# Shopfloor_HP_Molex_NEW.net
KiCad netlist of a schematic drawn in EAGLE
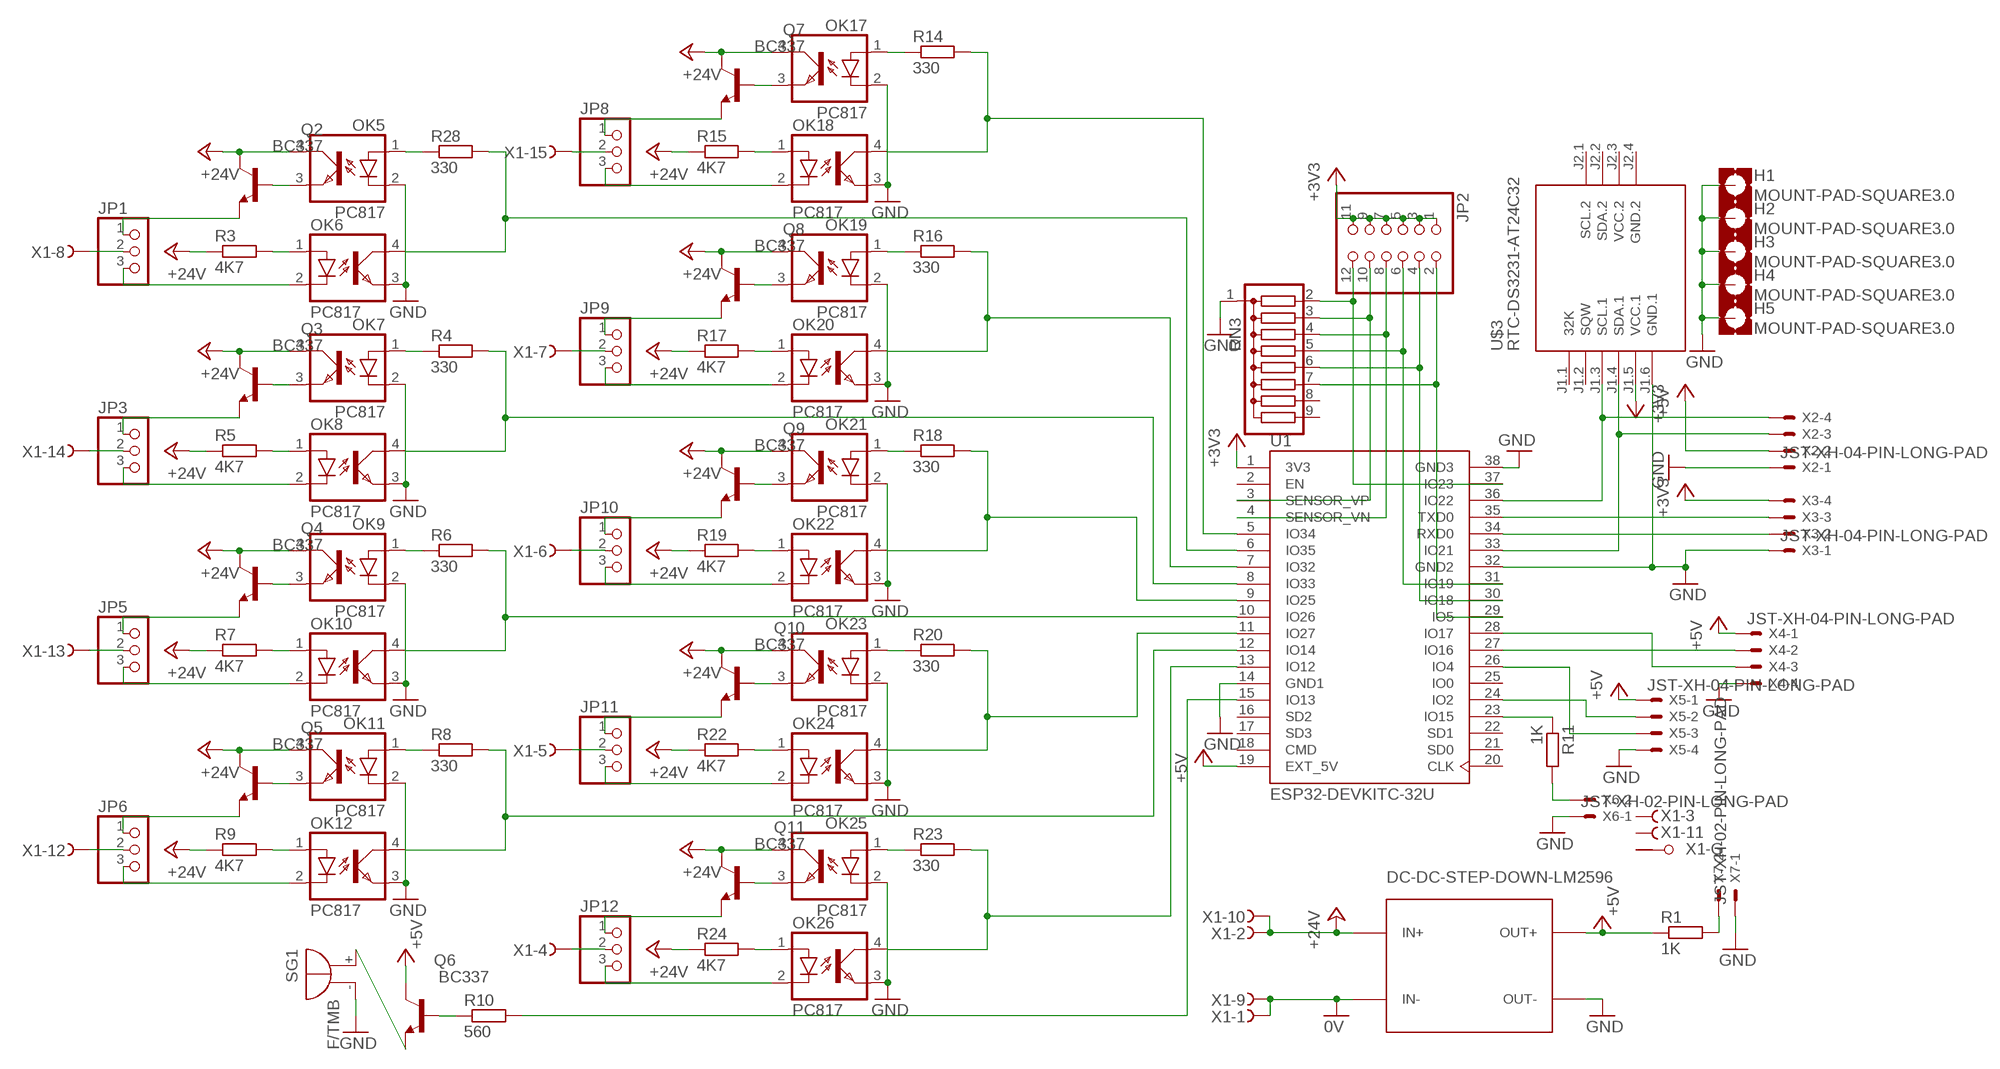
[diagram p0: schematic, sheet 1]

(export (version "E")
  (design (tool "Eeschema 10.0.6"))
  (components
    (comp (ref "H1")
      (value "MOUNT-PAD-SQUARE3.0")
      (footprint "eagle-import:3,0-PAD-SQUARE")
      (libsource (lib "eagle-import") (part "MOUNT-PAD-SQUARE3.0"))
    )
    (comp (ref "H2")
      (value "MOUNT-PAD-SQUARE3.0")
      (footprint "eagle-import:3,0-PAD-SQUARE")
      (libsource (lib "eagle-import") (part "MOUNT-PAD-SQUARE3.0"))
    )
    (comp (ref "H3")
      (value "MOUNT-PAD-SQUARE3.0")
      (footprint "eagle-import:3,0-PAD-SQUARE")
      (libsource (lib "eagle-import") (part "MOUNT-PAD-SQUARE3.0"))
    )
    (comp (ref "H4")
      (value "MOUNT-PAD-SQUARE3.0")
      (footprint "eagle-import:3,0-PAD-SQUARE")
      (libsource (lib "eagle-import") (part "MOUNT-PAD-SQUARE3.0"))
    )
    (comp (ref "H5")
      (value "MOUNT-PAD-SQUARE3.0")
      (footprint "eagle-import:3,0-PAD-SQUARE")
      (libsource (lib "eagle-import") (part "MOUNT-PAD-SQUARE3.0"))
    )
    (comp (ref "JP1")
      (value "PINHD-1X3")
      (footprint "eagle-import:1X03")
      (libsource (lib "eagle-import") (part "PINHD-1X3"))
    )
    (comp (ref "JP2")
      (value "PINHD-2X6")
      (footprint "eagle-import:2X06")
      (libsource (lib "eagle-import") (part "PINHD-2X6"))
    )
    (comp (ref "JP3")
      (value "PINHD-1X3")
      (footprint "eagle-import:1X03")
      (libsource (lib "eagle-import") (part "PINHD-1X3"))
    )
    (comp (ref "JP5")
      (value "PINHD-1X3")
      (footprint "eagle-import:1X03")
      (libsource (lib "eagle-import") (part "PINHD-1X3"))
    )
    (comp (ref "JP6")
      (value "PINHD-1X3")
      (footprint "eagle-import:1X03")
      (libsource (lib "eagle-import") (part "PINHD-1X3"))
    )
    (comp (ref "JP8")
      (value "PINHD-1X3")
      (footprint "eagle-import:1X03")
      (libsource (lib "eagle-import") (part "PINHD-1X3"))
    )
    (comp (ref "JP9")
      (value "PINHD-1X3")
      (footprint "eagle-import:1X03")
      (libsource (lib "eagle-import") (part "PINHD-1X3"))
    )
    (comp (ref "JP10")
      (value "PINHD-1X3")
      (footprint "eagle-import:1X03")
      (libsource (lib "eagle-import") (part "PINHD-1X3"))
    )
    (comp (ref "JP11")
      (value "PINHD-1X3")
      (footprint "eagle-import:1X03")
      (libsource (lib "eagle-import") (part "PINHD-1X3"))
    )
    (comp (ref "JP12")
      (value "PINHD-1X3")
      (footprint "eagle-import:1X03")
      (libsource (lib "eagle-import") (part "PINHD-1X3"))
    )
    (comp (ref "OK5")
      (value "PC817")
      (footprint "eagle-import:DIL04")
      (fields (field (name "MPN") "PC817X4J000F"))
      (libsource (lib "eagle-import") (part "PC817"))
    )
    (comp (ref "OK6")
      (value "PC817")
      (footprint "eagle-import:DIL04")
      (fields (field (name "MPN") "PC817X4J000F"))
      (libsource (lib "eagle-import") (part "PC817"))
    )
    (comp (ref "OK7")
      (value "PC817")
      (footprint "eagle-import:DIL04")
      (fields (field (name "MPN") "PC817X4J000F"))
      (libsource (lib "eagle-import") (part "PC817"))
    )
    (comp (ref "OK8")
      (value "PC817")
      (footprint "eagle-import:DIL04")
      (fields (field (name "MPN") "PC817X4J000F"))
      (libsource (lib "eagle-import") (part "PC817"))
    )
    (comp (ref "OK9")
      (value "PC817")
      (footprint "eagle-import:DIL04")
      (fields (field (name "MPN") "PC817X4J000F"))
      (libsource (lib "eagle-import") (part "PC817"))
    )
    (comp (ref "OK10")
      (value "PC817")
      (footprint "eagle-import:DIL04")
      (fields (field (name "MPN") "PC817X4J000F"))
      (libsource (lib "eagle-import") (part "PC817"))
    )
    (comp (ref "OK11")
      (value "PC817")
      (footprint "eagle-import:DIL04")
      (fields (field (name "MPN") "PC817X4J000F"))
      (libsource (lib "eagle-import") (part "PC817"))
    )
    (comp (ref "OK12")
      (value "PC817")
      (footprint "eagle-import:DIL04")
      (fields (field (name "MPN") "PC817X4J000F"))
      (libsource (lib "eagle-import") (part "PC817"))
    )
    (comp (ref "OK17")
      (value "PC817")
      (footprint "eagle-import:DIL04")
      (fields (field (name "MPN") "PC817X4J000F"))
      (libsource (lib "eagle-import") (part "PC817"))
    )
    (comp (ref "OK18")
      (value "PC817")
      (footprint "eagle-import:DIL04")
      (fields (field (name "MPN") "PC817X4J000F"))
      (libsource (lib "eagle-import") (part "PC817"))
    )
    (comp (ref "OK19")
      (value "PC817")
      (footprint "eagle-import:DIL04")
      (fields (field (name "MPN") "PC817X4J000F"))
      (libsource (lib "eagle-import") (part "PC817"))
    )
    (comp (ref "OK20")
      (value "PC817")
      (footprint "eagle-import:DIL04")
      (fields (field (name "MPN") "PC817X4J000F"))
      (libsource (lib "eagle-import") (part "PC817"))
    )
    (comp (ref "OK21")
      (value "PC817")
      (footprint "eagle-import:DIL04")
      (fields (field (name "MPN") "PC817X4J000F"))
      (libsource (lib "eagle-import") (part "PC817"))
    )
    (comp (ref "OK22")
      (value "PC817")
      (footprint "eagle-import:DIL04")
      (fields (field (name "MPN") "PC817X4J000F"))
      (libsource (lib "eagle-import") (part "PC817"))
    )
    (comp (ref "OK23")
      (value "PC817")
      (footprint "eagle-import:DIL04")
      (fields (field (name "MPN") "PC817X4J000F"))
      (libsource (lib "eagle-import") (part "PC817"))
    )
    (comp (ref "OK24")
      (value "PC817")
      (footprint "eagle-import:DIL04")
      (fields (field (name "MPN") "PC817X4J000F"))
      (libsource (lib "eagle-import") (part "PC817"))
    )
    (comp (ref "OK25")
      (value "PC817")
      (footprint "eagle-import:DIL04")
      (fields (field (name "MPN") "PC817X4J000F"))
      (libsource (lib "eagle-import") (part "PC817"))
    )
    (comp (ref "OK26")
      (value "PC817")
      (footprint "eagle-import:DIL04")
      (fields (field (name "MPN") "PC817X4J000F"))
      (libsource (lib "eagle-import") (part "PC817"))
    )
    (comp (ref "Q2")
      (value "BC337")
      (footprint "eagle-import:TO92")
      (libsource (lib "eagle-import") (part "BC337"))
    )
    (comp (ref "Q3")
      (value "BC337")
      (footprint "eagle-import:TO92")
      (libsource (lib "eagle-import") (part "BC337"))
    )
    (comp (ref "Q4")
      (value "BC337")
      (footprint "eagle-import:TO92")
      (libsource (lib "eagle-import") (part "BC337"))
    )
    (comp (ref "Q5")
      (value "BC337")
      (footprint "eagle-import:TO92")
      (libsource (lib "eagle-import") (part "BC337"))
    )
    (comp (ref "Q6")
      (value "BC337")
      (footprint "eagle-import:TO92")
      (libsource (lib "eagle-import") (part "BC337"))
    )
    (comp (ref "Q7")
      (value "BC337")
      (footprint "eagle-import:TO92")
      (libsource (lib "eagle-import") (part "BC337"))
    )
    (comp (ref "Q8")
      (value "BC337")
      (footprint "eagle-import:TO92")
      (libsource (lib "eagle-import") (part "BC337"))
    )
    (comp (ref "Q9")
      (value "BC337")
      (footprint "eagle-import:TO92")
      (libsource (lib "eagle-import") (part "BC337"))
    )
    (comp (ref "Q10")
      (value "BC337")
      (footprint "eagle-import:TO92")
      (libsource (lib "eagle-import") (part "BC337"))
    )
    (comp (ref "Q11")
      (value "BC337")
      (footprint "eagle-import:TO92")
      (libsource (lib "eagle-import") (part "BC337"))
    )
    (comp (ref "R1")
      (value "1K")
      (footprint "eagle-import:0207_7")
      (libsource (lib "eagle-import") (part "R-EU_0207/7"))
    )
    (comp (ref "R3")
      (value "4K7")
      (footprint "eagle-import:0207_7")
      (libsource (lib "eagle-import") (part "R-EU_0207/7"))
    )
    (comp (ref "R4")
      (value "330")
      (footprint "eagle-import:0207_7")
      (libsource (lib "eagle-import") (part "R-EU_0207/7"))
    )
    (comp (ref "R5")
      (value "4K7")
      (footprint "eagle-import:0207_7")
      (libsource (lib "eagle-import") (part "R-EU_0207/7"))
    )
    (comp (ref "R6")
      (value "330")
      (footprint "eagle-import:0207_7")
      (libsource (lib "eagle-import") (part "R-EU_0207/7"))
    )
    (comp (ref "R7")
      (value "4K7")
      (footprint "eagle-import:0207_7")
      (libsource (lib "eagle-import") (part "R-EU_0207/7"))
    )
    (comp (ref "R8")
      (value "330")
      (footprint "eagle-import:0207_7")
      (libsource (lib "eagle-import") (part "R-EU_0207/7"))
    )
    (comp (ref "R9")
      (value "4K7")
      (footprint "eagle-import:0207_7")
      (libsource (lib "eagle-import") (part "R-EU_0207/7"))
    )
    (comp (ref "R10")
      (value "560")
      (footprint "eagle-import:0207_7")
      (libsource (lib "eagle-import") (part "R-EU_0207/7"))
    )
    (comp (ref "R11")
      (value "1K")
      (footprint "eagle-import:0207_7")
      (libsource (lib "eagle-import") (part "R-EU_0207/7"))
    )
    (comp (ref "R14")
      (value "330")
      (footprint "eagle-import:0207_7")
      (libsource (lib "eagle-import") (part "R-EU_0207/7"))
    )
    (comp (ref "R15")
      (value "4K7")
      (footprint "eagle-import:0207_7")
      (libsource (lib "eagle-import") (part "R-EU_0207/7"))
    )
    (comp (ref "R16")
      (value "330")
      (footprint "eagle-import:0207_7")
      (libsource (lib "eagle-import") (part "R-EU_0207/7"))
    )
    (comp (ref "R17")
      (value "4K7")
      (footprint "eagle-import:0207_7")
      (libsource (lib "eagle-import") (part "R-EU_0207/7"))
    )
    (comp (ref "R18")
      (value "330")
      (footprint "eagle-import:0207_7")
      (libsource (lib "eagle-import") (part "R-EU_0207/7"))
    )
    (comp (ref "R19")
      (value "4K7")
      (footprint "eagle-import:0207_7")
      (libsource (lib "eagle-import") (part "R-EU_0207/7"))
    )
    (comp (ref "R20")
      (value "330")
      (footprint "eagle-import:0207_7")
      (libsource (lib "eagle-import") (part "R-EU_0207/7"))
    )
    (comp (ref "R22")
      (value "4K7")
      (footprint "eagle-import:0207_7")
      (libsource (lib "eagle-import") (part "R-EU_0207/7"))
    )
    (comp (ref "R23")
      (value "330")
      (footprint "eagle-import:0207_7")
      (libsource (lib "eagle-import") (part "R-EU_0207/7"))
    )
    (comp (ref "R24")
      (value "4K7")
      (footprint "eagle-import:0207_7")
      (libsource (lib "eagle-import") (part "R-EU_0207/7"))
    )
    (comp (ref "R28")
      (value "330")
      (footprint "eagle-import:0207_7")
      (libsource (lib "eagle-import") (part "R-EU_0207/7"))
    )
    (comp (ref "RN3")
      (value "G08R")
      (footprint "eagle-import:SIL9")
      (libsource (lib "eagle-import") (part "G08R"))
    )
    (comp (ref "SG1")
      (value "F/TMB")
      (footprint "eagle-import:F_TMB")
      (libsource (lib "eagle-import") (part "F/TMB"))
    )
    (comp (ref "U$1")
      (value "DC-DC-STEP-DOWN-LM2596")
      (footprint "eagle-import:DC-DC-STEP-DOWN-LM2596")
      (libsource (lib "eagle-import") (part "DC-DC-STEP-DOWN-LM2596"))
    )
    (comp (ref "U$3")
      (value "RTC-DS3231-AT24C32")
      (footprint "eagle-import:RTC-DS3231-AT24C32")
      (libsource (lib "eagle-import") (part "RTC-DS3231-AT24C32"))
    )
    (comp (ref "U1")
      (value "ESP32-DEVKITC-32U")
      (footprint "eagle-import:MODULE_ESP32-DEVKITC-32U")
      (fields (field (name "MF") "Espressif Systems"))
      (libsource (lib "eagle-import") (part "ESP32-DEVKITC-32U"))
    )
    (comp (ref "X1")
      (value "F15HPS")
      (footprint "eagle-import:F15HP")
      (libsource (lib "eagle-import") (part "F15HPS"))
    )
    (comp (ref "X2")
      (value "JST-XH-04-PIN-LONG-PAD")
      (footprint "eagle-import:JST-XH-04-PACKAGE-LONG-PAD")
      (libsource (lib "eagle-import") (part "JST-XH-04-PIN-LONG-PAD"))
    )
    (comp (ref "X3")
      (value "JST-XH-04-PIN-LONG-PAD")
      (footprint "eagle-import:JST-XH-04-PACKAGE-LONG-PAD")
      (libsource (lib "eagle-import") (part "JST-XH-04-PIN-LONG-PAD"))
    )
    (comp (ref "X4")
      (value "JST-XH-04-PIN-LONG-PAD")
      (footprint "eagle-import:JST-XH-04-PACKAGE-LONG-PAD")
      (libsource (lib "eagle-import") (part "JST-XH-04-PIN-LONG-PAD"))
    )
    (comp (ref "X5")
      (value "JST-XH-04-PIN-LONG-PAD")
      (footprint "eagle-import:JST-XH-04-PACKAGE-LONG-PAD")
      (libsource (lib "eagle-import") (part "JST-XH-04-PIN-LONG-PAD"))
    )
    (comp (ref "X6")
      (value "JST-XH-02-PIN-LONG-PAD")
      (footprint "eagle-import:JST-XH-02-PACKAGE-LONG-PAD")
      (libsource (lib "eagle-import") (part "JST-XH-02-PIN-LONG-PAD"))
    )
    (comp (ref "X7")
      (value "JST-XH-02-PIN-LONG-PAD")
      (footprint "eagle-import:JST-XH-02-PACKAGE-LONG-PAD")
      (libsource (lib "eagle-import") (part "JST-XH-02-PIN-LONG-PAD"))
    )
  )
  (nets
    (net (code "1") (name "+3V3") (class "Default")
      (node (ref "JP2") (pin "1") (pinfunction "1_1") (pintype "passive"))
      (node (ref "JP2") (pin "11") (pinfunction "11_11") (pintype "passive"))
      (node (ref "JP2") (pin "3") (pinfunction "3_3") (pintype "passive"))
      (node (ref "JP2") (pin "5") (pinfunction "5_5") (pintype "passive"))
      (node (ref "JP2") (pin "7") (pinfunction "7_7") (pintype "passive"))
      (node (ref "JP2") (pin "9") (pinfunction "9_9") (pintype "passive"))
      (node (ref "U$3") (pin "J1.5") (pinfunction "VCC.1_J1.5") (pintype "power_in"))
      (node (ref "U1") (pin "1") (pinfunction "3V3_1") (pintype "power_in"))
      (node (ref "X3") (pin "4") (pinfunction "S_4") (pintype "passive"))
    )
    (net (code "2") (name "+5V") (class "Default")
      (node (ref "Q6") (pin "3") (pinfunction "C_3") (pintype "passive"))
      (node (ref "R1") (pin "1") (pinfunction "1_1") (pintype "passive"))
      (node (ref "U$1") (pin "OUT+") (pinfunction "OUT+_OUT+") (pintype "bidirectional"))
      (node (ref "U1") (pin "19") (pinfunction "EXT_5V_19") (pintype "power_in"))
      (node (ref "X2") (pin "2") (pinfunction "S_2") (pintype "passive"))
      (node (ref "X4") (pin "1") (pinfunction "S_1") (pintype "passive"))
      (node (ref "X5") (pin "1") (pinfunction "S_1") (pintype "passive"))
    )
    (net (code "3") (name "+24V") (class "Default")
      (node (ref "OK11") (pin "4") (pinfunction "COL_4") (pintype "passive"))
      (node (ref "OK17") (pin "4") (pinfunction "COL_4") (pintype "passive"))
      (node (ref "OK19") (pin "4") (pinfunction "COL_4") (pintype "passive"))
      (node (ref "OK21") (pin "4") (pinfunction "COL_4") (pintype "passive"))
      (node (ref "OK23") (pin "4") (pinfunction "COL_4") (pintype "passive"))
      (node (ref "OK25") (pin "4") (pinfunction "COL_4") (pintype "passive"))
      (node (ref "OK5") (pin "4") (pinfunction "COL_4") (pintype "passive"))
      (node (ref "OK7") (pin "4") (pinfunction "COL_4") (pintype "passive"))
      (node (ref "OK9") (pin "4") (pinfunction "COL_4") (pintype "passive"))
      (node (ref "Q10") (pin "3") (pinfunction "C_3") (pintype "passive"))
      (node (ref "Q11") (pin "3") (pinfunction "C_3") (pintype "passive"))
      (node (ref "Q2") (pin "3") (pinfunction "C_3") (pintype "passive"))
      (node (ref "Q3") (pin "3") (pinfunction "C_3") (pintype "passive"))
      (node (ref "Q4") (pin "3") (pinfunction "C_3") (pintype "passive"))
      (node (ref "Q5") (pin "3") (pinfunction "C_3") (pintype "passive"))
      (node (ref "Q7") (pin "3") (pinfunction "C_3") (pintype "passive"))
      (node (ref "Q8") (pin "3") (pinfunction "C_3") (pintype "passive"))
      (node (ref "Q9") (pin "3") (pinfunction "C_3") (pintype "passive"))
      (node (ref "R15") (pin "1") (pinfunction "1_1") (pintype "passive"))
      (node (ref "R17") (pin "1") (pinfunction "1_1") (pintype "passive"))
      (node (ref "R19") (pin "1") (pinfunction "1_1") (pintype "passive"))
      (node (ref "R22") (pin "1") (pinfunction "1_1") (pintype "passive"))
      (node (ref "R24") (pin "1") (pinfunction "1_1") (pintype "passive"))
      (node (ref "R3") (pin "1") (pinfunction "1_1") (pintype "passive"))
      (node (ref "R5") (pin "1") (pinfunction "1_1") (pintype "passive"))
      (node (ref "R7") (pin "1") (pinfunction "1_1") (pintype "passive"))
      (node (ref "R9") (pin "1") (pinfunction "1_1") (pintype "passive"))
      (node (ref "U$1") (pin "IN+") (pinfunction "IN+_IN+") (pintype "bidirectional"))
      (node (ref "X1") (pin "10") (pinfunction "F_10") (pintype "passive"))
      (node (ref "X1") (pin "2") (pinfunction "F_2") (pintype "passive"))
    )
    (net (code "4") (name "/GND.2") (class "Default")
      (node (ref "U$3") (pin "J2.4") (pinfunction "GND.2_J2.4") (pintype "power_in"))
    )
    (net (code "5") (name "/VCC.2") (class "Default")
      (node (ref "U$3") (pin "J2.3") (pinfunction "VCC.2_J2.3") (pintype "power_in"))
    )
    (net (code "6") (name "0V") (class "Default")
      (node (ref "U$1") (pin "IN-") (pinfunction "IN-_IN-") (pintype "bidirectional"))
      (node (ref "X1") (pin "1") (pinfunction "F_1") (pintype "passive"))
      (node (ref "X1") (pin "9") (pinfunction "F_9") (pintype "passive"))
    )
    (net (code "7") (name "GND") (class "Default")
      (node (ref "H1") (pin "B3,0") (pinfunction "MOUNT_B3,0") (pintype "passive"))
      (node (ref "H2") (pin "B3,0") (pinfunction "MOUNT_B3,0") (pintype "passive"))
      (node (ref "H3") (pin "B3,0") (pinfunction "MOUNT_B3,0") (pintype "passive"))
      (node (ref "H4") (pin "B3,0") (pinfunction "MOUNT_B3,0") (pintype "passive"))
      (node (ref "H5") (pin "B3,0") (pinfunction "MOUNT_B3,0") (pintype "passive"))
      (node (ref "OK10") (pin "3") (pinfunction "EMIT_3") (pintype "passive"))
      (node (ref "OK11") (pin "2") (pinfunction "C_2") (pintype "passive"))
      (node (ref "OK12") (pin "3") (pinfunction "EMIT_3") (pintype "passive"))
      (node (ref "OK17") (pin "2") (pinfunction "C_2") (pintype "passive"))
      (node (ref "OK18") (pin "3") (pinfunction "EMIT_3") (pintype "passive"))
      (node (ref "OK19") (pin "2") (pinfunction "C_2") (pintype "passive"))
      (node (ref "OK20") (pin "3") (pinfunction "EMIT_3") (pintype "passive"))
      (node (ref "OK21") (pin "2") (pinfunction "C_2") (pintype "passive"))
      (node (ref "OK22") (pin "3") (pinfunction "EMIT_3") (pintype "passive"))
      (node (ref "OK23") (pin "2") (pinfunction "C_2") (pintype "passive"))
      (node (ref "OK24") (pin "3") (pinfunction "EMIT_3") (pintype "passive"))
      (node (ref "OK25") (pin "2") (pinfunction "C_2") (pintype "passive"))
      (node (ref "OK26") (pin "3") (pinfunction "EMIT_3") (pintype "passive"))
      (node (ref "OK5") (pin "2") (pinfunction "C_2") (pintype "passive"))
      (node (ref "OK6") (pin "3") (pinfunction "EMIT_3") (pintype "passive"))
      (node (ref "OK7") (pin "2") (pinfunction "C_2") (pintype "passive"))
      (node (ref "OK8") (pin "3") (pinfunction "EMIT_3") (pintype "passive"))
      (node (ref "OK9") (pin "2") (pinfunction "C_2") (pintype "passive"))
      (node (ref "RN3") (pin "1") (pinfunction "1_1") (pintype "passive"))
      (node (ref "SG1") (pin "-") (pinfunction "-_-") (pintype "passive"))
      (node (ref "U$1") (pin "OUT-") (pinfunction "OUT-_OUT-") (pintype "bidirectional"))
      (node (ref "U$3") (pin "J1.6") (pinfunction "GND.1_J1.6") (pintype "power_in"))
      (node (ref "U1") (pin "14") (pinfunction "GND1_14") (pintype "power_in"))
      (node (ref "U1") (pin "32") (pinfunction "GND2_32") (pintype "power_in"))
      (node (ref "U1") (pin "38") (pinfunction "GND3_38") (pintype "power_in"))
      (node (ref "X2") (pin "1") (pinfunction "S_1") (pintype "passive"))
      (node (ref "X3") (pin "1") (pinfunction "S_1") (pintype "passive"))
      (node (ref "X4") (pin "4") (pinfunction "S_4") (pintype "passive"))
      (node (ref "X5") (pin "4") (pinfunction "S_4") (pintype "passive"))
      (node (ref "X6") (pin "1") (pinfunction "S_1") (pintype "passive"))
      (node (ref "X7") (pin "1") (pinfunction "S_1") (pintype "passive"))
    )
    (net (code "8") (name "Net-(OK5-A)") (class "Default")
      (node (ref "OK5") (pin "1") (pinfunction "A_1") (pintype "passive"))
      (node (ref "R28") (pin "1") (pinfunction "1_1") (pintype "passive"))
    )
    (net (code "9") (name "Net-(OK5-EMIT)") (class "Default")
      (node (ref "OK5") (pin "3") (pinfunction "EMIT_3") (pintype "passive"))
      (node (ref "Q2") (pin "2") (pinfunction "B_2") (pintype "passive"))
    )
    (net (code "10") (name "Net-(OK6-A)") (class "Default")
      (node (ref "OK6") (pin "1") (pinfunction "A_1") (pintype "passive"))
      (node (ref "R3") (pin "2") (pinfunction "2_2") (pintype "passive"))
    )
    (net (code "11") (name "Net-(OK6-C)") (class "Default")
      (node (ref "JP1") (pin "3") (pinfunction "3_3") (pintype "passive"))
      (node (ref "OK6") (pin "2") (pinfunction "C_2") (pintype "passive"))
    )
    (net (code "12") (name "Net-(OK6-COL)") (class "Default")
      (node (ref "OK6") (pin "4") (pinfunction "COL_4") (pintype "passive"))
      (node (ref "R28") (pin "2") (pinfunction "2_2") (pintype "passive"))
      (node (ref "U1") (pin "6") (pinfunction "IO35_6") (pintype "bidirectional"))
    )
    (net (code "13") (name "Net-(OK7-A)") (class "Default")
      (node (ref "OK7") (pin "1") (pinfunction "A_1") (pintype "passive"))
      (node (ref "R4") (pin "1") (pinfunction "1_1") (pintype "passive"))
    )
    (net (code "14") (name "Net-(OK7-EMIT)") (class "Default")
      (node (ref "OK7") (pin "3") (pinfunction "EMIT_3") (pintype "passive"))
      (node (ref "Q3") (pin "2") (pinfunction "B_2") (pintype "passive"))
    )
    (net (code "15") (name "Net-(OK8-A)") (class "Default")
      (node (ref "OK8") (pin "1") (pinfunction "A_1") (pintype "passive"))
      (node (ref "R5") (pin "2") (pinfunction "2_2") (pintype "passive"))
    )
    (net (code "16") (name "Net-(OK8-C)") (class "Default")
      (node (ref "JP3") (pin "3") (pinfunction "3_3") (pintype "passive"))
      (node (ref "OK8") (pin "2") (pinfunction "C_2") (pintype "passive"))
    )
    (net (code "17") (name "Net-(OK8-COL)") (class "Default")
      (node (ref "OK8") (pin "4") (pinfunction "COL_4") (pintype "passive"))
      (node (ref "R4") (pin "2") (pinfunction "2_2") (pintype "passive"))
      (node (ref "U1") (pin "8") (pinfunction "IO33_8") (pintype "bidirectional"))
    )
    (net (code "18") (name "Net-(OK9-A)") (class "Default")
      (node (ref "OK9") (pin "1") (pinfunction "A_1") (pintype "passive"))
      (node (ref "R6") (pin "1") (pinfunction "1_1") (pintype "passive"))
    )
    (net (code "19") (name "Net-(OK9-EMIT)") (class "Default")
      (node (ref "OK9") (pin "3") (pinfunction "EMIT_3") (pintype "passive"))
      (node (ref "Q4") (pin "2") (pinfunction "B_2") (pintype "passive"))
    )
    (net (code "20") (name "Net-(OK10-A)") (class "Default")
      (node (ref "OK10") (pin "1") (pinfunction "A_1") (pintype "passive"))
      (node (ref "R7") (pin "2") (pinfunction "2_2") (pintype "passive"))
    )
    (net (code "21") (name "Net-(OK10-C)") (class "Default")
      (node (ref "JP5") (pin "3") (pinfunction "3_3") (pintype "passive"))
      (node (ref "OK10") (pin "2") (pinfunction "C_2") (pintype "passive"))
    )
    (net (code "22") (name "Net-(OK10-COL)") (class "Default")
      (node (ref "OK10") (pin "4") (pinfunction "COL_4") (pintype "passive"))
      (node (ref "R6") (pin "2") (pinfunction "2_2") (pintype "passive"))
      (node (ref "U1") (pin "10") (pinfunction "IO26_10") (pintype "bidirectional"))
    )
    (net (code "23") (name "Net-(OK11-A)") (class "Default")
      (node (ref "OK11") (pin "1") (pinfunction "A_1") (pintype "passive"))
      (node (ref "R8") (pin "1") (pinfunction "1_1") (pintype "passive"))
    )
    (net (code "24") (name "Net-(OK11-EMIT)") (class "Default")
      (node (ref "OK11") (pin "3") (pinfunction "EMIT_3") (pintype "passive"))
      (node (ref "Q5") (pin "2") (pinfunction "B_2") (pintype "passive"))
    )
    (net (code "25") (name "Net-(OK12-A)") (class "Default")
      (node (ref "OK12") (pin "1") (pinfunction "A_1") (pintype "passive"))
      (node (ref "R9") (pin "2") (pinfunction "2_2") (pintype "passive"))
    )
    (net (code "26") (name "Net-(OK12-C)") (class "Default")
      (node (ref "JP6") (pin "3") (pinfunction "3_3") (pintype "passive"))
      (node (ref "OK12") (pin "2") (pinfunction "C_2") (pintype "passive"))
    )
    (net (code "27") (name "Net-(OK12-COL)") (class "Default")
      (node (ref "OK12") (pin "4") (pinfunction "COL_4") (pintype "passive"))
      (node (ref "R8") (pin "2") (pinfunction "2_2") (pintype "passive"))
      (node (ref "U1") (pin "12") (pinfunction "IO14_12") (pintype "bidirectional"))
    )
    (net (code "28") (name "Net-(OK17-A)") (class "Default")
      (node (ref "OK17") (pin "1") (pinfunction "A_1") (pintype "passive"))
      (node (ref "R14") (pin "1") (pinfunction "1_1") (pintype "passive"))
    )
    (net (code "29") (name "Net-(OK17-EMIT)") (class "Default")
      (node (ref "OK17") (pin "3") (pinfunction "EMIT_3") (pintype "passive"))
      (node (ref "Q7") (pin "2") (pinfunction "B_2") (pintype "passive"))
    )
    (net (code "30") (name "Net-(OK18-A)") (class "Default")
      (node (ref "OK18") (pin "1") (pinfunction "A_1") (pintype "passive"))
      (node (ref "R15") (pin "2") (pinfunction "2_2") (pintype "passive"))
    )
    (net (code "31") (name "Net-(OK18-C)") (class "Default")
      (node (ref "JP8") (pin "3") (pinfunction "3_3") (pintype "passive"))
      (node (ref "OK18") (pin "2") (pinfunction "C_2") (pintype "passive"))
    )
    (net (code "32") (name "Net-(OK18-COL)") (class "Default")
      (node (ref "OK18") (pin "4") (pinfunction "COL_4") (pintype "passive"))
      (node (ref "R14") (pin "2") (pinfunction "2_2") (pintype "passive"))
      (node (ref "U1") (pin "5") (pinfunction "IO34_5") (pintype "bidirectional"))
    )
    (net (code "33") (name "Net-(OK19-A)") (class "Default")
      (node (ref "OK19") (pin "1") (pinfunction "A_1") (pintype "passive"))
      (node (ref "R16") (pin "1") (pinfunction "1_1") (pintype "passive"))
    )
    (net (code "34") (name "Net-(OK19-EMIT)") (class "Default")
      (node (ref "OK19") (pin "3") (pinfunction "EMIT_3") (pintype "passive"))
      (node (ref "Q8") (pin "2") (pinfunction "B_2") (pintype "passive"))
    )
    (net (code "35") (name "Net-(OK20-A)") (class "Default")
      (node (ref "OK20") (pin "1") (pinfunction "A_1") (pintype "passive"))
      (node (ref "R17") (pin "2") (pinfunction "2_2") (pintype "passive"))
    )
    (net (code "36") (name "Net-(OK20-C)") (class "Default")
      (node (ref "JP9") (pin "3") (pinfunction "3_3") (pintype "passive"))
      (node (ref "OK20") (pin "2") (pinfunction "C_2") (pintype "passive"))
    )
    (net (code "37") (name "Net-(OK20-COL)") (class "Default")
      (node (ref "OK20") (pin "4") (pinfunction "COL_4") (pintype "passive"))
      (node (ref "R16") (pin "2") (pinfunction "2_2") (pintype "passive"))
      (node (ref "U1") (pin "7") (pinfunction "IO32_7") (pintype "bidirectional"))
    )
    (net (code "38") (name "Net-(OK21-A)") (class "Default")
      (node (ref "OK21") (pin "1") (pinfunction "A_1") (pintype "passive"))
      (node (ref "R18") (pin "1") (pinfunction "1_1") (pintype "passive"))
    )
    (net (code "39") (name "Net-(OK21-EMIT)") (class "Default")
      (node (ref "OK21") (pin "3") (pinfunction "EMIT_3") (pintype "passive"))
      (node (ref "Q9") (pin "2") (pinfunction "B_2") (pintype "passive"))
    )
    (net (code "40") (name "Net-(OK22-A)") (class "Default")
      (node (ref "OK22") (pin "1") (pinfunction "A_1") (pintype "passive"))
      (node (ref "R19") (pin "2") (pinfunction "2_2") (pintype "passive"))
    )
    (net (code "41") (name "Net-(OK22-C)") (class "Default")
      (node (ref "JP10") (pin "3") (pinfunction "3_3") (pintype "passive"))
      (node (ref "OK22") (pin "2") (pinfunction "C_2") (pintype "passive"))
    )
    (net (code "42") (name "Net-(OK22-COL)") (class "Default")
      (node (ref "OK22") (pin "4") (pinfunction "COL_4") (pintype "passive"))
      (node (ref "R18") (pin "2") (pinfunction "2_2") (pintype "passive"))
      (node (ref "U1") (pin "9") (pinfunction "IO25_9") (pintype "bidirectional"))
    )
    (net (code "43") (name "Net-(OK23-A)") (class "Default")
      (node (ref "OK23") (pin "1") (pinfunction "A_1") (pintype "passive"))
      (node (ref "R20") (pin "1") (pinfunction "1_1") (pintype "passive"))
    )
    (net (code "44") (name "Net-(OK23-EMIT)") (class "Default")
      (node (ref "OK23") (pin "3") (pinfunction "EMIT_3") (pintype "passive"))
      (node (ref "Q10") (pin "2") (pinfunction "B_2") (pintype "passive"))
    )
    (net (code "45") (name "Net-(OK24-A)") (class "Default")
      (node (ref "OK24") (pin "1") (pinfunction "A_1") (pintype "passive"))
      (node (ref "R22") (pin "2") (pinfunction "2_2") (pintype "passive"))
    )
    (net (code "46") (name "Net-(OK24-C)") (class "Default")
      (node (ref "JP11") (pin "3") (pinfunction "3_3") (pintype "passive"))
      (node (ref "OK24") (pin "2") (pinfunction "C_2") (pintype "passive"))
    )
    (net (code "47") (name "Net-(OK24-COL)") (class "Default")
      (node (ref "OK24") (pin "4") (pinfunction "COL_4") (pintype "passive"))
      (node (ref "R20") (pin "2") (pinfunction "2_2") (pintype "passive"))
      (node (ref "U1") (pin "11") (pinfunction "IO27_11") (pintype "bidirectional"))
    )
    (net (code "48") (name "Net-(OK25-A)") (class "Default")
      (node (ref "OK25") (pin "1") (pinfunction "A_1") (pintype "passive"))
      (node (ref "R23") (pin "1") (pinfunction "1_1") (pintype "passive"))
    )
    (net (code "49") (name "Net-(OK25-EMIT)") (class "Default")
      (node (ref "OK25") (pin "3") (pinfunction "EMIT_3") (pintype "passive"))
      (node (ref "Q11") (pin "2") (pinfunction "B_2") (pintype "passive"))
    )
    (net (code "50") (name "Net-(OK26-A)") (class "Default")
      (node (ref "OK26") (pin "1") (pinfunction "A_1") (pintype "passive"))
      (node (ref "R24") (pin "2") (pinfunction "2_2") (pintype "passive"))
    )
    (net (code "51") (name "Net-(OK26-C)") (class "Default")
      (node (ref "JP12") (pin "3") (pinfunction "3_3") (pintype "passive"))
      (node (ref "OK26") (pin "2") (pinfunction "C_2") (pintype "passive"))
    )
    (net (code "52") (name "Net-(OK26-COL)") (class "Default")
      (node (ref "OK26") (pin "4") (pinfunction "COL_4") (pintype "passive"))
      (node (ref "R23") (pin "2") (pinfunction "2_2") (pintype "passive"))
      (node (ref "U1") (pin "13") (pinfunction "IO12_13") (pintype "bidirectional"))
    )
    (net (code "53") (name "Net-(Q2-E)") (class "Default")
      (node (ref "JP1") (pin "1") (pinfunction "1_1") (pintype "passive"))
      (node (ref "Q2") (pin "1") (pinfunction "E_1") (pintype "passive"))
    )
    (net (code "54") (name "Net-(Q3-E)") (class "Default")
      (node (ref "JP3") (pin "1") (pinfunction "1_1") (pintype "passive"))
      (node (ref "Q3") (pin "1") (pinfunction "E_1") (pintype "passive"))
    )
    (net (code "55") (name "Net-(Q4-E)") (class "Default")
      (node (ref "JP5") (pin "1") (pinfunction "1_1") (pintype "passive"))
      (node (ref "Q4") (pin "1") (pinfunction "E_1") (pintype "passive"))
    )
    (net (code "56") (name "Net-(Q5-E)") (class "Default")
      (node (ref "JP6") (pin "1") (pinfunction "1_1") (pintype "passive"))
      (node (ref "Q5") (pin "1") (pinfunction "E_1") (pintype "passive"))
    )
    (net (code "57") (name "Net-(Q6-B)") (class "Default")
      (node (ref "Q6") (pin "2") (pinfunction "B_2") (pintype "passive"))
      (node (ref "R10") (pin "1") (pinfunction "1_1") (pintype "passive"))
    )
    (net (code "58") (name "Net-(Q6-E)") (class "Default")
      (node (ref "Q6") (pin "1") (pinfunction "E_1") (pintype "passive"))
      (node (ref "SG1") (pin "+") (pinfunction "+_+") (pintype "passive"))
    )
    (net (code "59") (name "Net-(Q7-E)") (class "Default")
      (node (ref "JP8") (pin "1") (pinfunction "1_1") (pintype "passive"))
      (node (ref "Q7") (pin "1") (pinfunction "E_1") (pintype "passive"))
    )
    (net (code "60") (name "Net-(Q8-E)") (class "Default")
      (node (ref "JP9") (pin "1") (pinfunction "1_1") (pintype "passive"))
      (node (ref "Q8") (pin "1") (pinfunction "E_1") (pintype "passive"))
    )
    (net (code "61") (name "Net-(Q9-E)") (class "Default")
      (node (ref "JP10") (pin "1") (pinfunction "1_1") (pintype "passive"))
      (node (ref "Q9") (pin "1") (pinfunction "E_1") (pintype "passive"))
    )
    (net (code "62") (name "Net-(Q10-E)") (class "Default")
      (node (ref "JP11") (pin "1") (pinfunction "1_1") (pintype "passive"))
      (node (ref "Q10") (pin "1") (pinfunction "E_1") (pintype "passive"))
    )
    (net (code "63") (name "Net-(Q11-E)") (class "Default")
      (node (ref "JP12") (pin "1") (pinfunction "1_1") (pintype "passive"))
      (node (ref "Q11") (pin "1") (pinfunction "E_1") (pintype "passive"))
    )
    (net (code "64") (name "Net-(U$3-SCL.1)") (class "Default")
      (node (ref "U$3") (pin "J1.3") (pinfunction "SCL.1_J1.3") (pintype "bidirectional"))
      (node (ref "U1") (pin "36") (pinfunction "IO22_36") (pintype "bidirectional"))
      (node (ref "X2") (pin "4") (pinfunction "S_4") (pintype "passive"))
    )
    (net (code "65") (name "Net-(U$3-SDA.1)") (class "Default")
      (node (ref "U$3") (pin "J1.4") (pinfunction "SDA.1_J1.4") (pintype "bidirectional"))
      (node (ref "U1") (pin "33") (pinfunction "IO21_33") (pintype "bidirectional"))
      (node (ref "X2") (pin "3") (pinfunction "S_3") (pintype "passive"))
    )
    (net (code "66") (name "Net-(U1-IO2)") (class "Default")
      (node (ref "U1") (pin "24") (pinfunction "IO2_24") (pintype "bidirectional"))
      (node (ref "X5") (pin "2") (pinfunction "S_2") (pintype "passive"))
    )
    (net (code "67") (name "Net-(U1-IO4)") (class "Default")
      (node (ref "U1") (pin "26") (pinfunction "IO4_26") (pintype "bidirectional"))
      (node (ref "X5") (pin "3") (pinfunction "S_3") (pintype "passive"))
    )
    (net (code "68") (name "Net-(U1-IO5)") (class "Default")
      (node (ref "JP2") (pin "2") (pinfunction "2_2") (pintype "passive"))
      (node (ref "RN3") (pin "7") (pinfunction "7_7") (pintype "passive"))
      (node (ref "U1") (pin "29") (pinfunction "IO5_29") (pintype "bidirectional"))
    )
    (net (code "69") (name "Net-(U1-IO13)") (class "Default")
      (node (ref "R10") (pin "2") (pinfunction "2_2") (pintype "passive"))
      (node (ref "U1") (pin "15") (pinfunction "IO13_15") (pintype "bidirectional"))
    )
    (net (code "70") (name "Net-(U1-IO15)") (class "Default")
      (node (ref "R11") (pin "1") (pinfunction "1_1") (pintype "passive"))
      (node (ref "U1") (pin "23") (pinfunction "IO15_23") (pintype "bidirectional"))
    )
    (net (code "71") (name "Net-(U1-IO16)") (class "Default")
      (node (ref "U1") (pin "27") (pinfunction "IO16_27") (pintype "bidirectional"))
      (node (ref "X4") (pin "2") (pinfunction "S_2") (pintype "passive"))
    )
    (net (code "72") (name "Net-(U1-IO17)") (class "Default")
      (node (ref "U1") (pin "28") (pinfunction "IO17_28") (pintype "bidirectional"))
      (node (ref "X4") (pin "3") (pinfunction "S_3") (pintype "passive"))
    )
    (net (code "73") (name "Net-(U1-IO18)") (class "Default")
      (node (ref "JP2") (pin "4") (pinfunction "4_4") (pintype "passive"))
      (node (ref "RN3") (pin "6") (pinfunction "6_6") (pintype "passive"))
      (node (ref "U1") (pin "30") (pinfunction "IO18_30") (pintype "bidirectional"))
    )
    (net (code "74") (name "Net-(U1-IO19)") (class "Default")
      (node (ref "JP2") (pin "6") (pinfunction "6_6") (pintype "passive"))
      (node (ref "RN3") (pin "5") (pinfunction "5_5") (pintype "passive"))
      (node (ref "U1") (pin "31") (pinfunction "IO19_31") (pintype "bidirectional"))
    )
    (net (code "75") (name "Net-(U1-IO23)") (class "Default")
      (node (ref "JP2") (pin "12") (pinfunction "12_12") (pintype "passive"))
      (node (ref "RN3") (pin "2") (pinfunction "2_2") (pintype "passive"))
      (node (ref "U1") (pin "37") (pinfunction "IO23_37") (pintype "bidirectional"))
    )
    (net (code "76") (name "Net-(U1-RXD0)") (class "Default")
      (node (ref "U1") (pin "34") (pinfunction "RXD0_34") (pintype "input"))
      (node (ref "X3") (pin "2") (pinfunction "S_2") (pintype "passive"))
    )
    (net (code "77") (name "Net-(U1-SENSOR_VN)") (class "Default")
      (node (ref "JP2") (pin "8") (pinfunction "8_8") (pintype "passive"))
      (node (ref "RN3") (pin "4") (pinfunction "4_4") (pintype "passive"))
      (node (ref "U1") (pin "4") (pinfunction "SENSOR_VN_4") (pintype "input"))
    )
    (net (code "78") (name "Net-(U1-SENSOR_VP)") (class "Default")
      (node (ref "JP2") (pin "10") (pinfunction "10_10") (pintype "passive"))
      (node (ref "RN3") (pin "3") (pinfunction "3_3") (pintype "passive"))
      (node (ref "U1") (pin "3") (pinfunction "SENSOR_VP_3") (pintype "input"))
    )
    (net (code "79") (name "Net-(U1-TXD0)") (class "Default")
      (node (ref "U1") (pin "35") (pinfunction "TXD0_35") (pintype "output"))
      (node (ref "X3") (pin "3") (pinfunction "S_3") (pintype "passive"))
    )
    (net (code "80") (name "Net-(X1D-F)") (class "Default")
      (node (ref "JP6") (pin "2") (pinfunction "2_2") (pintype "passive"))
      (node (ref "X1") (pin "12") (pinfunction "F_12") (pintype "passive"))
    )
    (net (code "81") (name "Net-(X1E-F)") (class "Default")
      (node (ref "JP5") (pin "2") (pinfunction "2_2") (pintype "passive"))
      (node (ref "X1") (pin "13") (pinfunction "F_13") (pintype "passive"))
    )
    (net (code "82") (name "Net-(X1F-F)") (class "Default")
      (node (ref "JP3") (pin "2") (pinfunction "2_2") (pintype "passive"))
      (node (ref "X1") (pin "14") (pinfunction "F_14") (pintype "passive"))
    )
    (net (code "83") (name "Net-(X1G-F)") (class "Default")
      (node (ref "JP8") (pin "2") (pinfunction "2_2") (pintype "passive"))
      (node (ref "X1") (pin "15") (pinfunction "F_15") (pintype "passive"))
    )
    (net (code "84") (name "Net-(X1J-F)") (class "Default")
      (node (ref "JP12") (pin "2") (pinfunction "2_2") (pintype "passive"))
      (node (ref "X1") (pin "4") (pinfunction "F_4") (pintype "passive"))
    )
    (net (code "85") (name "Net-(X1K-F)") (class "Default")
      (node (ref "JP11") (pin "2") (pinfunction "2_2") (pintype "passive"))
      (node (ref "X1") (pin "5") (pinfunction "F_5") (pintype "passive"))
    )
    (net (code "86") (name "Net-(X1L-F)") (class "Default")
      (node (ref "JP10") (pin "2") (pinfunction "2_2") (pintype "passive"))
      (node (ref "X1") (pin "6") (pinfunction "F_6") (pintype "passive"))
    )
    (net (code "87") (name "Net-(X1M-F)") (class "Default")
      (node (ref "JP9") (pin "2") (pinfunction "2_2") (pintype "passive"))
      (node (ref "X1") (pin "7") (pinfunction "F_7") (pintype "passive"))
    )
    (net (code "88") (name "Net-(X1N-F)") (class "Default")
      (node (ref "JP1") (pin "2") (pinfunction "2_2") (pintype "passive"))
      (node (ref "X1") (pin "8") (pinfunction "F_8") (pintype "passive"))
    )
    (net (code "89") (name "Net-(X6B-S)") (class "Default")
      (node (ref "R11") (pin "2") (pinfunction "2_2") (pintype "passive"))
      (node (ref "X6") (pin "2") (pinfunction "S_2") (pintype "passive"))
    )
    (net (code "90") (name "Net-(X7B-S)") (class "Default")
      (node (ref "R1") (pin "2") (pinfunction "2_2") (pintype "passive"))
      (node (ref "X7") (pin "2") (pinfunction "S_2") (pintype "passive"))
    )
    (net (code "91") (name "unconnected-(RN3-Pad8)") (class "Default")
      (node (ref "RN3") (pin "8") (pinfunction "8_8") (pintype "passive"))
    )
    (net (code "92") (name "unconnected-(RN3-Pad9)") (class "Default")
      (node (ref "RN3") (pin "9") (pinfunction "9_9") (pintype "passive"))
    )
    (net (code "93") (name "unconnected-(U$3-32K-PadJ1.1)") (class "Default")
      (node (ref "U$3") (pin "J1.1") (pinfunction "32K_J1.1") (pintype "bidirectional"))
    )
    (net (code "94") (name "unconnected-(U$3-SCL.2-PadJ2.1)") (class "Default")
      (node (ref "U$3") (pin "J2.1") (pinfunction "SCL.2_J2.1") (pintype "bidirectional"))
    )
    (net (code "95") (name "unconnected-(U$3-SDA.2-PadJ2.2)") (class "Default")
      (node (ref "U$3") (pin "J2.2") (pinfunction "SDA.2_J2.2") (pintype "bidirectional"))
    )
    (net (code "96") (name "unconnected-(U$3-SQW-PadJ1.2)") (class "Default")
      (node (ref "U$3") (pin "J1.2") (pinfunction "SQW_J1.2") (pintype "bidirectional"))
    )
    (net (code "97") (name "unconnected-(U1-CLK-Pad20)") (class "Default")
      (node (ref "U1") (pin "20") (pinfunction "CLK_20") (pintype "input"))
    )
    (net (code "98") (name "unconnected-(U1-CMD-Pad18)") (class "Default")
      (node (ref "U1") (pin "18") (pinfunction "CMD_18") (pintype "bidirectional"))
    )
    (net (code "99") (name "unconnected-(U1-EN-Pad2)") (class "Default")
      (node (ref "U1") (pin "2") (pinfunction "EN_2") (pintype "input"))
    )
    (net (code "100") (name "unconnected-(U1-IO0-Pad25)") (class "Default")
      (node (ref "U1") (pin "25") (pinfunction "IO0_25") (pintype "bidirectional"))
    )
    (net (code "101") (name "unconnected-(U1-SD0-Pad21)") (class "Default")
      (node (ref "U1") (pin "21") (pinfunction "SD0_21") (pintype "bidirectional"))
    )
    (net (code "102") (name "unconnected-(U1-SD1-Pad22)") (class "Default")
      (node (ref "U1") (pin "22") (pinfunction "SD1_22") (pintype "bidirectional"))
    )
    (net (code "103") (name "unconnected-(U1-SD2-Pad16)") (class "Default")
      (node (ref "U1") (pin "16") (pinfunction "SD2_16") (pintype "bidirectional"))
    )
    (net (code "104") (name "unconnected-(U1-SD3-Pad17)") (class "Default")
      (node (ref "U1") (pin "17") (pinfunction "SD3_17") (pintype "bidirectional"))
    )
    (net (code "105") (name "unconnected-(X1-PadG1)") (class "Default")
      (node (ref "X1") (pin "G1") (pinfunction "G1_G1") (pintype "passive"))
    )
    (net (code "106") (name "unconnected-(X1-PadG2)") (class "Default")
      (node (ref "X1") (pin "G2") (pinfunction "G2_G2") (pintype "passive"))
    )
    (net (code "107") (name "unconnected-(X1C-F-Pad11)") (class "Default")
      (node (ref "X1") (pin "11") (pinfunction "F_11") (pintype "passive"))
    )
    (net (code "108") (name "unconnected-(X1I-F-Pad3)") (class "Default")
      (node (ref "X1") (pin "3") (pinfunction "F_3") (pintype "passive"))
    )
  )
)
